# Power_Supply.net
KiCad netlist of a schematic drawn in Altium Designer
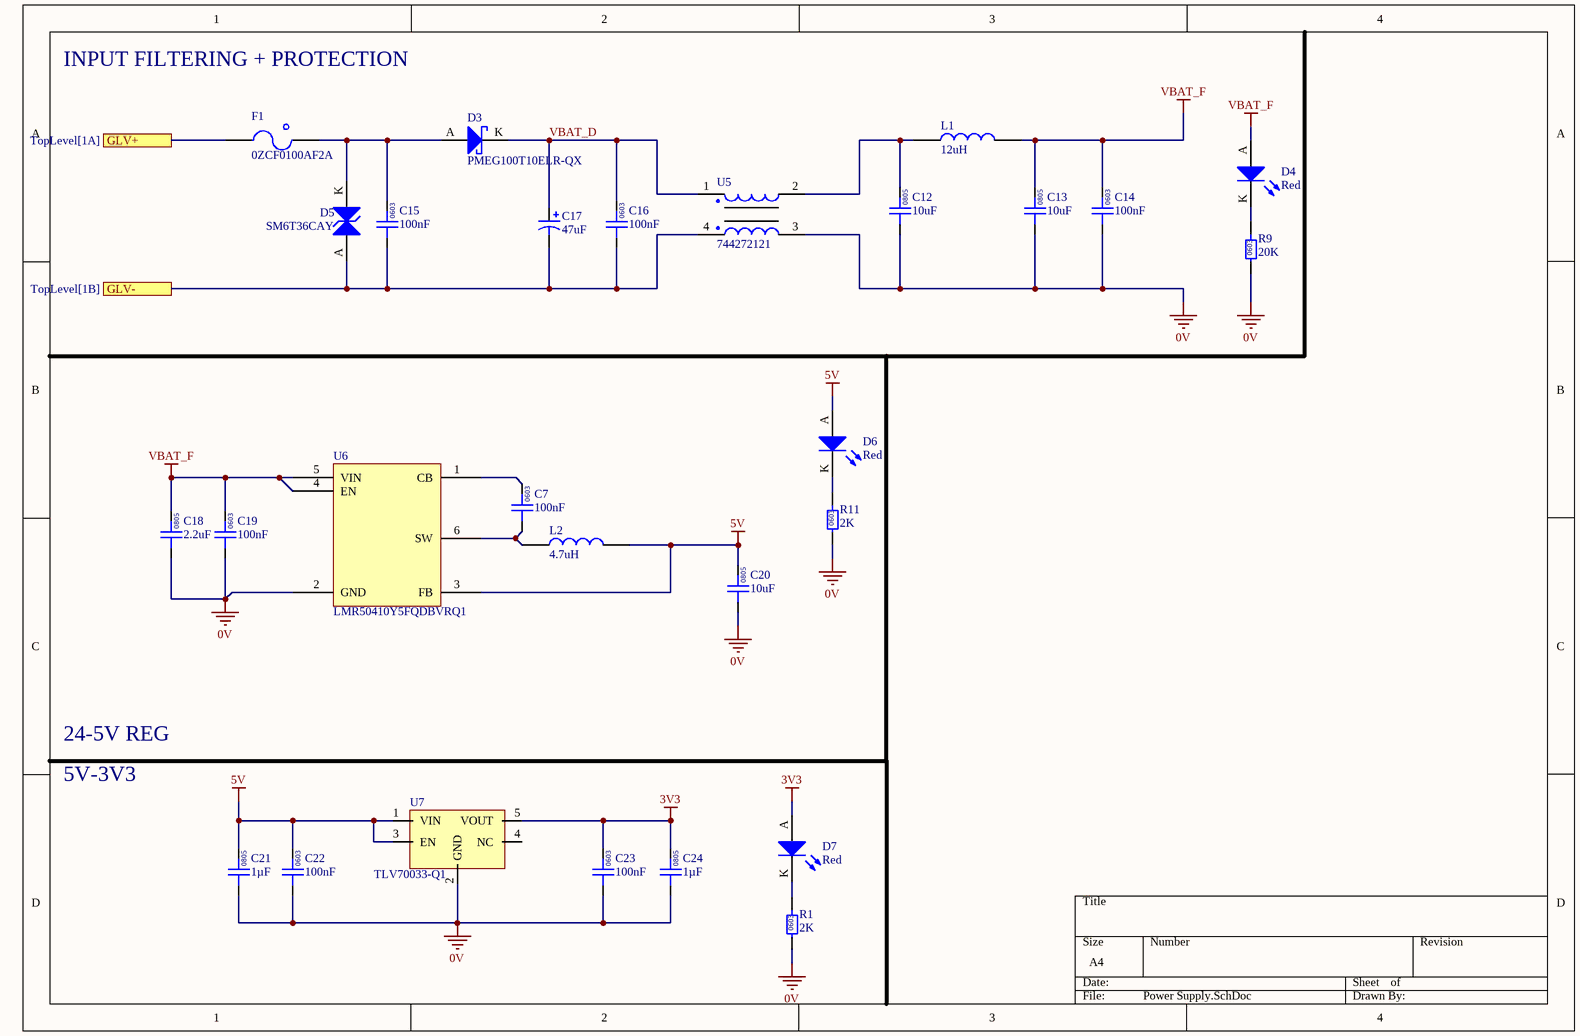
[diagram p0: Power Supply.SchDoc]

(export (version "E")
  (design (tool "Eeschema 10.0.6"))
  (components
    (comp (ref "C7")
      (value "100nF")
      (footprint "0603")
      (fields
        (field (name "PART NUMBER") "GCM188L81H104KA57D")
        (field (name "MANUFACTURER") "muRata")
        (field (name "TOLERANCE") "±10%")
      )
      (libsource (lib "ts_standard_library") (part "Capacitor 0603"))
    )
    (comp (ref "C12")
      (value "10uF")
      (footprint "0805")
      (fields
        (field (name "PART NUMBER") "GRM21BR6YA106KE43L")
        (field (name "MANUFACTURER") "muRata")
        (field (name "TOLERANCE") "10%")
      )
      (libsource (lib "ts_standard_library") (part "Capacitor 0805"))
    )
    (comp (ref "C13")
      (value "10uF")
      (footprint "0805")
      (fields
        (field (name "PART NUMBER") "GRM21BR6YA106KE43L")
        (field (name "MANUFACTURER") "muRata")
        (field (name "TOLERANCE") "10%")
      )
      (libsource (lib "ts_standard_library") (part "Capacitor 0805"))
    )
    (comp (ref "C14")
      (value "100nF")
      (footprint "0603")
      (fields
        (field (name "PART NUMBER") "GCM188L81H104KA57D")
        (field (name "MANUFACTURER") "muRata")
        (field (name "TOLERANCE") "±10%")
      )
      (libsource (lib "ts_standard_library") (part "Capacitor 0603"))
    )
    (comp (ref "C15")
      (value "100nF")
      (footprint "0603")
      (fields
        (field (name "PART NUMBER") "GCM188L81H104KA57D")
        (field (name "MANUFACTURER") "muRata")
        (field (name "TOLERANCE") "±10%")
      )
      (libsource (lib "ts_standard_library") (part "Capacitor 0603"))
    )
    (comp (ref "C16")
      (value "100nF")
      (footprint "0603")
      (fields
        (field (name "PART NUMBER") "GCM188L81H104KA57D")
        (field (name "MANUFACTURER") "muRata")
        (field (name "TOLERANCE") "±10%")
      )
      (libsource (lib "ts_standard_library") (part "Capacitor 0603"))
    )
    (comp (ref "C17")
      (value "47uF")
      (footprint "CHEMI-CON ELCO")
      (fields (field (name "PART NUMBER") "HHXA350ARA470MF61G"))
      (libsource (lib "ts_standard_library") (part "Capacitor (Polarised)"))
    )
    (comp (ref "C18")
      (value "2.2uF")
      (footprint "0805")
      (fields
        (field (name "PART NUMBER") "GRM21BR71E225KE11L")
        (field (name "MANUFACTURER") "Murata Electronics")
        (field (name "TOLERANCE") "±10%")
      )
      (libsource (lib "ts_standard_library") (part "Capacitor 0805"))
    )
    (comp (ref "C19")
      (value "100nF")
      (footprint "0603")
      (fields
        (field (name "PART NUMBER") "GCM188L81H104KA57D")
        (field (name "MANUFACTURER") "muRata")
        (field (name "TOLERANCE") "±10%")
      )
      (libsource (lib "ts_standard_library") (part "Capacitor 0603"))
    )
    (comp (ref "C20")
      (value "10uF")
      (footprint "0805")
      (fields
        (field (name "PART NUMBER") "GRM21BR6YA106KE43L")
        (field (name "MANUFACTURER") "muRata")
        (field (name "TOLERANCE") "10%")
      )
      (libsource (lib "ts_standard_library") (part "Capacitor 0805"))
    )
    (comp (ref "C21")
      (value "1µF")
      (footprint "0805")
      (fields
        (field (name "PART NUMBER") "GCM21BR71H105KA03L")
        (field (name "MANUFACTURER") "muRata")
        (field (name "TOLERANCE") "±10%")
      )
      (libsource (lib "ts_standard_library") (part "Capacitor 0805"))
    )
    (comp (ref "C22")
      (value "100nF")
      (footprint "0603")
      (fields
        (field (name "PART NUMBER") "GCM188L81H104KA57D")
        (field (name "MANUFACTURER") "muRata")
        (field (name "TOLERANCE") "±10%")
      )
      (libsource (lib "ts_standard_library") (part "Capacitor 0603"))
    )
    (comp (ref "C23")
      (value "100nF")
      (footprint "0603")
      (fields
        (field (name "PART NUMBER") "GCM188L81H104KA57D")
        (field (name "MANUFACTURER") "muRata")
        (field (name "TOLERANCE") "±10%")
      )
      (libsource (lib "ts_standard_library") (part "Capacitor 0603"))
    )
    (comp (ref "C24")
      (value "1µF")
      (footprint "0805")
      (fields
        (field (name "PART NUMBER") "GCM21BR71H105KA03L")
        (field (name "MANUFACTURER") "muRata")
        (field (name "TOLERANCE") "±10%")
      )
      (libsource (lib "ts_standard_library") (part "Capacitor 0805"))
    )
    (comp (ref "D3")
      (value "PMEG100T10ELR-QX")
      (footprint "NXP SOD123W")
      (fields
        (field (name "MANUFACTURER") "Nexperia USA Inc.")
        (field (name "DIGIKEY PART NUMBER") "1727-PMEG100T10ELR-QXCT-ND")
      )
      (libsource (lib "ts_standard_library") (part "Diode (Schottky)"))
    )
    (comp (ref "D4")
      (value "Red")
      (footprint "0805 LED")
      (description "Red LED Indication - Discrete 1.75V 0805 (2012 Metric)")
      (fields (field (name "PART NUMBER") "SML-210LTT86") (field (name "MANUFACTURER") "ROHM Semiconductor"))
      (libsource (lib "ts_standard_library") (part "LED"))
    )
    (comp (ref "D5")
      (value "SM6T36CAY")
      (footprint "ST SMB DIODE")
      (fields
        (field (name "MANUFACTURER") "STMicroelectronics")
        (field (name "DIGIKEY PART NUMBER") "497-10804-1-ND")
      )
      (libsource (lib "ts_standard_library") (part "TVS (Bidirectional)"))
    )
    (comp (ref "D6")
      (value "Red")
      (footprint "0805 LED")
      (description "Red LED Indication - Discrete 1.75V 0805 (2012 Metric)")
      (fields (field (name "PART NUMBER") "SML-210LTT86") (field (name "MANUFACTURER") "ROHM Semiconductor"))
      (libsource (lib "ts_standard_library") (part "LED"))
    )
    (comp (ref "D7")
      (value "Red")
      (footprint "0805 LED")
      (description "Red LED Indication - Discrete 1.75V 0805 (2012 Metric)")
      (fields (field (name "PART NUMBER") "SML-210LTT86") (field (name "MANUFACTURER") "ROHM Semiconductor"))
      (libsource (lib "ts_standard_library") (part "LED"))
    )
    (comp (ref "F1")
      (value "0ZCF0100AF2A")
      (footprint "2920")
      (description "PTC RESET FUSE 60V 1A 292")
      (fields
        (field (name "MANUFACTURER") "Littelfuse Inc.")
        (field (name "DIGIKEY PART NUMBER") "507-2070-1-ND")
      )
      (libsource (lib "ts_standard_library") (part "PTC Fuse"))
    )
    (comp (ref "L1")
      (value "12uH")
      (footprint "1812")
      (fields
        (field (name "PART NUMBER") "RLS-126")
        (field (name "MANUFACTURER") "Recom")
        (field (name "TOLERANCE") "0.2")
      )
      (libsource (lib "ts_20-standard-library") (part "Inductor"))
    )
    (comp (ref "L2")
      (value "4.7uH")
      (footprint "SRN3015TA-4R7M")
      (fields
        (field (name "PART NUMBER") "SRN4018-4R7M")
        (field (name "MANUFACTURER") "Bourns")
        (field (name "TOLERANCE") "0.2")
      )
      (libsource (lib "ts_standard_library") (part "Inductor"))
    )
    (comp (ref "R1")
      (value "2K")
      (footprint "0603")
      (fields
        (field (name "PART NUMBER") "RC0603FR-072KL")
        (field (name "MANUFACTURER") "YAGEO")
        (field (name "TOLERANCE") "0.01")
      )
      (libsource (lib "ts_standard_library") (part "Resistor 0603"))
    )
    (comp (ref "R9")
      (value "20K")
      (footprint "0603")
      (fields
        (field (name "PART NUMBER") "RC0603FR-0720KL")
        (field (name "MANUFACTURER") "YAGEO")
        (field (name "TOLERANCE") "0.01")
      )
      (libsource (lib "ts_standard_library") (part "Resistor 0603"))
    )
    (comp (ref "R11")
      (value "2K")
      (footprint "0603")
      (fields
        (field (name "PART NUMBER") "RC0603FR-072KL")
        (field (name "MANUFACTURER") "YAGEO")
        (field (name "TOLERANCE") "0.01")
      )
      (libsource (lib "ts_standard_library") (part "Resistor 0603"))
    )
    (comp (ref "U5")
      (value "744272121")
      (footprint "Wurth 4-PC Pad")
      (fields
        (field (name "MANUFACTURER") "Wurth Electronics Inc")
        (field (name "DIGIKEY PART NUMBER") "732-1489-1-ND")
      )
      (libsource (lib "ts_standard_library") (part "CM Choke"))
    )
    (comp (ref "U6")
      (value "LMR50410Y5FQDBVRQ1")
      (footprint "TI-SOT23-6")
      (description "IC REG BUCK 5V 1A SOT23-6")
      (fields (field (name "PART NUMBER") "LMR50410-Q1") (field (name "MANUFACTURER") "Texas Instruments"))
      (libsource (lib "ts_standard_library") (part "LMR50410Y5FQDBVRQ1"))
    )
    (comp (ref "U7")
      (value "TLV70033-Q1")
      (footprint "TI SOT-23-5")
      (description "IC REG LINEAR 3.3V 200MA SOT23-5")
      (fields
        (field (name "MANUFACTURER") "Texas Instruments")
        (field (name "DIGIKEY PART NUMBER") "296-27780-1-ND")
      )
      (libsource (lib "ts_standard_library") (part "TLV70033-Q1"))
    )
  )
  (nets
    (net (code "1") (name "/GLV+") (class "Default")
      (node (ref "F1") (pin "1") (pinfunction "1_1") (pintype "passive"))
    )
    (net (code "2") (name "/GLV-") (class "Default")
      (node (ref "C15") (pin "1") (pinfunction "1_1") (pintype "passive"))
      (node (ref "C16") (pin "1") (pinfunction "1_1") (pintype "passive"))
      (node (ref "C17") (pin "1") (pinfunction "1_1") (pintype "passive"))
      (node (ref "D5") (pin "A") (pinfunction "A_A") (pintype "passive"))
      (node (ref "U5") (pin "4") (pinfunction "4_4") (pintype "passive"))
    )
    (net (code "3") (name "/VBAT_D") (class "Default")
      (node (ref "C16") (pin "2") (pinfunction "2_2") (pintype "passive"))
      (node (ref "C17") (pin "2") (pinfunction "2_2") (pintype "passive"))
      (node (ref "D3") (pin "K") (pinfunction "K_K") (pintype "passive"))
      (node (ref "U5") (pin "1") (pinfunction "1_1") (pintype "passive"))
    )
    (net (code "4") (name "0V") (class "Default")
      (node (ref "C12") (pin "1") (pinfunction "1_1") (pintype "passive"))
      (node (ref "C13") (pin "1") (pinfunction "1_1") (pintype "passive"))
      (node (ref "C14") (pin "1") (pinfunction "1_1") (pintype "passive"))
      (node (ref "C18") (pin "1") (pinfunction "1_1") (pintype "passive"))
      (node (ref "C19") (pin "1") (pinfunction "1_1") (pintype "passive"))
      (node (ref "C20") (pin "1") (pinfunction "1_1") (pintype "passive"))
      (node (ref "C21") (pin "1") (pinfunction "1_1") (pintype "passive"))
      (node (ref "C22") (pin "1") (pinfunction "1_1") (pintype "passive"))
      (node (ref "C23") (pin "1") (pinfunction "1_1") (pintype "passive"))
      (node (ref "C24") (pin "1") (pinfunction "1_1") (pintype "passive"))
      (node (ref "R1") (pin "1") (pinfunction "1_1") (pintype "passive"))
      (node (ref "R11") (pin "1") (pinfunction "1_1") (pintype "passive"))
      (node (ref "R9") (pin "1") (pinfunction "1_1") (pintype "passive"))
      (node (ref "U5") (pin "3") (pinfunction "3_3") (pintype "power_in"))
      (node (ref "U6") (pin "2") (pinfunction "GND_2") (pintype "passive"))
      (node (ref "U7") (pin "2") (pinfunction "GND_2") (pintype "passive"))
    )
    (net (code "5") (name "3V3") (class "Default")
      (node (ref "C23") (pin "2") (pinfunction "2_2") (pintype "passive"))
      (node (ref "C24") (pin "2") (pinfunction "2_2") (pintype "passive"))
      (node (ref "D7") (pin "A") (pinfunction "A_A") (pintype "passive"))
      (node (ref "U7") (pin "5") (pinfunction "VOUT_5") (pintype "passive"))
    )
    (net (code "6") (name "5V") (class "Default")
      (node (ref "C20") (pin "2") (pinfunction "2_2") (pintype "passive"))
      (node (ref "C21") (pin "2") (pinfunction "2_2") (pintype "passive"))
      (node (ref "C22") (pin "2") (pinfunction "2_2") (pintype "passive"))
      (node (ref "D6") (pin "A") (pinfunction "A_A") (pintype "passive"))
      (node (ref "L2") (pin "1") (pinfunction "1_1") (pintype "passive"))
      (node (ref "U6") (pin "3") (pinfunction "FB_3") (pintype "passive"))
      (node (ref "U7") (pin "1") (pinfunction "VIN_1") (pintype "passive"))
      (node (ref "U7") (pin "3") (pinfunction "EN_3") (pintype "passive"))
    )
    (net (code "7") (name "Net-(C12-Pad2)") (class "Default")
      (node (ref "C12") (pin "2") (pinfunction "2_2") (pintype "passive"))
      (node (ref "L1") (pin "2") (pinfunction "2_2") (pintype "passive"))
      (node (ref "U5") (pin "2") (pinfunction "2_2") (pintype "passive"))
    )
    (net (code "8") (name "Net-(C15-Pad2)") (class "Default")
      (node (ref "C15") (pin "2") (pinfunction "2_2") (pintype "passive"))
      (node (ref "D3") (pin "A") (pinfunction "A_A") (pintype "passive"))
      (node (ref "D5") (pin "K") (pinfunction "K_K") (pintype "passive"))
      (node (ref "F1") (pin "2") (pinfunction "2_2") (pintype "passive"))
    )
    (net (code "9") (name "Net-(D4-PadK)") (class "Default")
      (node (ref "D4") (pin "K") (pinfunction "K_K") (pintype "passive"))
      (node (ref "R9") (pin "2") (pinfunction "2_2") (pintype "passive"))
    )
    (net (code "10") (name "Net-(D6-PadK)") (class "Default")
      (node (ref "D6") (pin "K") (pinfunction "K_K") (pintype "passive"))
      (node (ref "R11") (pin "2") (pinfunction "2_2") (pintype "passive"))
    )
    (net (code "11") (name "Net-(D7-PadK)") (class "Default")
      (node (ref "D7") (pin "K") (pinfunction "K_K") (pintype "passive"))
      (node (ref "R1") (pin "2") (pinfunction "2_2") (pintype "passive"))
    )
    (net (code "12") (name "Net-(U6-CB)") (class "Default")
      (node (ref "C7") (pin "2") (pinfunction "2_2") (pintype "passive"))
      (node (ref "U6") (pin "1") (pinfunction "CB_1") (pintype "passive"))
    )
    (net (code "13") (name "Net-(U6-SW)") (class "Default")
      (node (ref "C7") (pin "1") (pinfunction "1_1") (pintype "passive"))
      (node (ref "L2") (pin "2") (pinfunction "2_2") (pintype "passive"))
      (node (ref "U6") (pin "6") (pinfunction "SW_6") (pintype "passive"))
    )
    (net (code "14") (name "VBAT_F") (class "Default")
      (node (ref "C13") (pin "2") (pinfunction "2_2") (pintype "passive"))
      (node (ref "C14") (pin "2") (pinfunction "2_2") (pintype "passive"))
      (node (ref "C18") (pin "2") (pinfunction "2_2") (pintype "passive"))
      (node (ref "C19") (pin "2") (pinfunction "2_2") (pintype "passive"))
      (node (ref "D4") (pin "A") (pinfunction "A_A") (pintype "passive"))
      (node (ref "L1") (pin "1") (pinfunction "1_1") (pintype "passive"))
      (node (ref "U6") (pin "4") (pinfunction "EN_4") (pintype "passive"))
      (node (ref "U6") (pin "5") (pinfunction "VIN_5") (pintype "passive"))
    )
    (net (code "15") (name "unconnected-(U7-NC-Pad4)") (class "Default")
      (node (ref "U7") (pin "4") (pinfunction "NC_4") (pintype "passive"))
    )
  )
)
